# PID_MPS.net
KiCad netlist of a schematic drawn in EAGLE
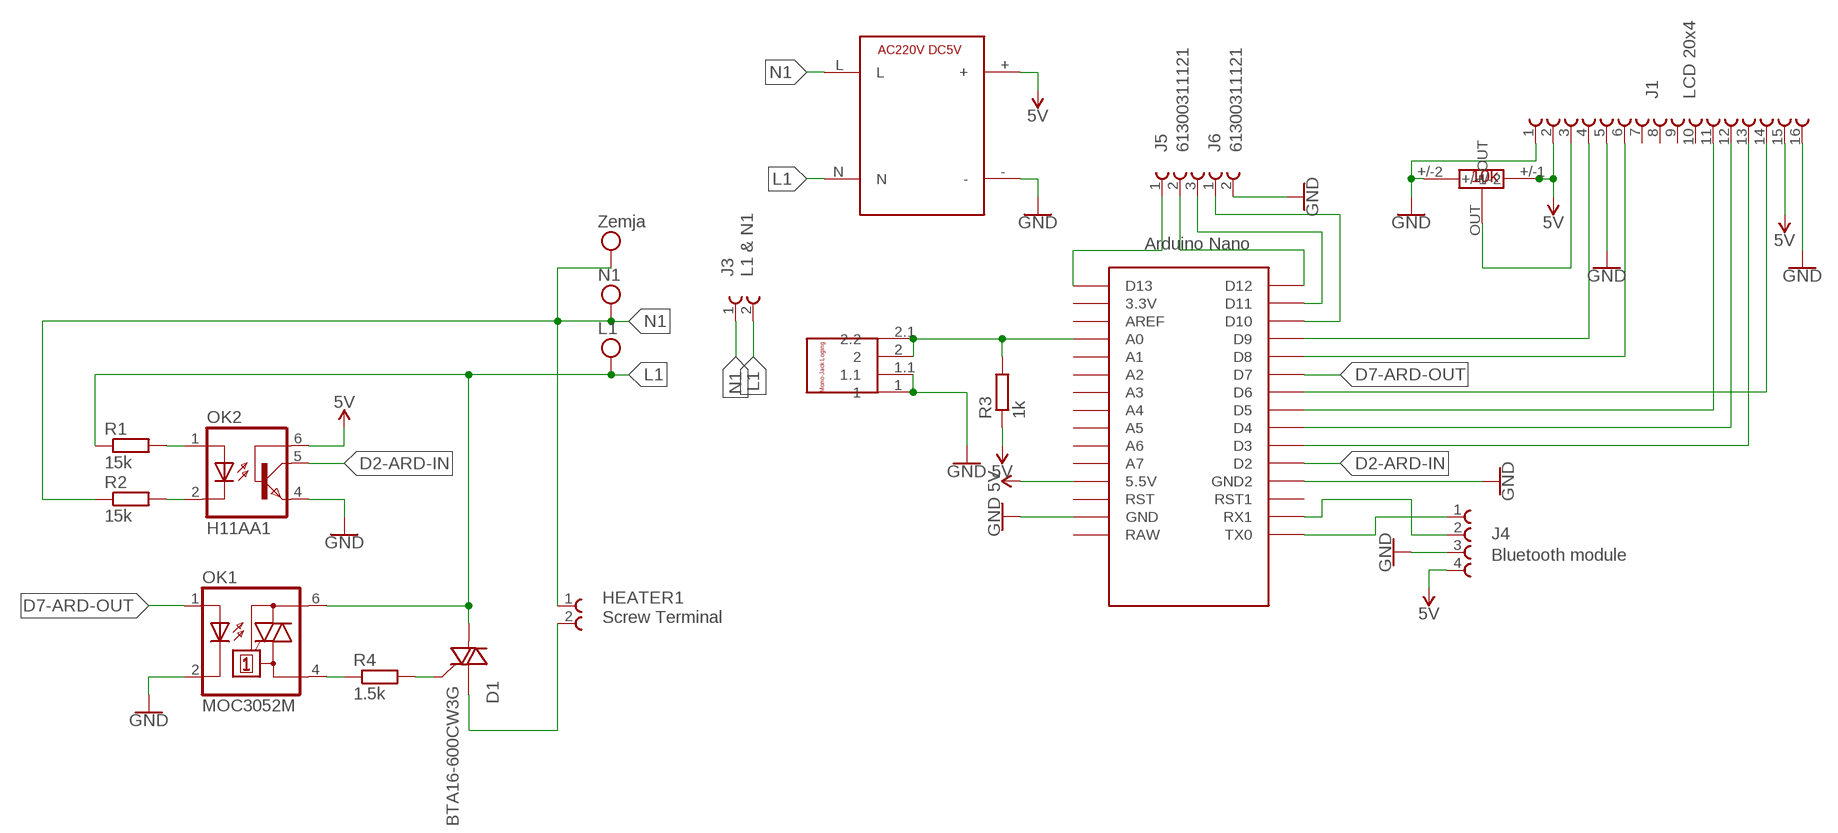
[diagram p0: schematic, sheet 1]

(export (version "E")
  (design (tool "Eeschema 10.0.6"))
  (components
    (comp (ref "D1")
      (value "BTA16-600CW3G")
      (footprint "eagle-import:TO254P1028X482X1968-3")
      (fields (field (name "MF") "Littelfuse Inc."))
      (libsource (lib "eagle-import") (part "BTA16-600CW3G"))
    )
    (comp (ref "HEATER1")
      (value "Screw Terminal")
      (footprint "eagle-import:691102710002")
      (fields (field (name "MF") "Wurth Electronics") (field (name "MP") "691102710002"))
      (libsource (lib "eagle-import") (part "691102710002"))
    )
    (comp (ref "J1")
      (value "LCD 20x4")
      (footprint "eagle-import:61301611121")
      (fields (field (name "MF") "Wurth Electronics") (field (name "MP") "61301611121"))
      (libsource (lib "eagle-import") (part "61301611121"))
    )
    (comp (ref "J3")
      (value "L1 & N1")
      (footprint "eagle-import:691102710002")
      (fields (field (name "MF") "Wurth Electronics") (field (name "MP") "691102710002"))
      (libsource (lib "eagle-import") (part "691102710002"))
    )
    (comp (ref "J4")
      (value "Bluetooth module")
      (footprint "eagle-import:61300411121")
      (fields (field (name "MF") "Wurth") (field (name "MP") "61300411121"))
      (libsource (lib "eagle-import") (part "61300411121"))
    )
    (comp (ref "J5")
      (value "61300311121")
      (footprint "eagle-import:61300311121")
      (fields (field (name "MF") "Wurth Electronics"))
      (libsource (lib "eagle-import") (part "61300311121 Letvici (cesel 3pin)_61300311121"))
    )
    (comp (ref "J6")
      (value "61300311121")
      (footprint "eagle-import:61300311121")
      (fields (field (name "MF") "Wurth Electronics"))
      (libsource (lib "eagle-import") (part "61300311121"))
    )
    (comp (ref "OK1")
      (value "MOC3052M")
      (footprint "eagle-import:DIL06")
      (fields (field (name "MF") "FAIRCHILD SEMICONDUCTOR") (field (name "MPN") "MOC3042-M"))
      (libsource (lib "eagle-import") (part "MOC3042M"))
    )
    (comp (ref "OK2")
      (value "H11AA1")
      (footprint "eagle-import:DIL06")
      (fields (field (name "MPN") "H11A1-M"))
      (libsource (lib "eagle-import") (part "H11A?M1"))
    )
    (comp (ref "R1")
      (value "15k")
      (footprint "eagle-import:0207_10")
      (libsource (lib "eagle-import") (part "R0207/10"))
    )
    (comp (ref "R2")
      (value "15k")
      (footprint "eagle-import:0207_10")
      (libsource (lib "eagle-import") (part "R0207/10"))
    )
    (comp (ref "R3")
      (value "1k")
      (footprint "eagle-import:0207_10")
      (libsource (lib "eagle-import") (part "R0207/10"))
    )
    (comp (ref "R4")
      (value "1.5k")
      (footprint "eagle-import:0207_10")
      (libsource (lib "eagle-import") (part "R0207/10"))
    )
    (comp (ref "U$1")
      (value "NANO")
      (footprint "eagle-import:NANO")
      (libsource (lib "eagle-import") (part "NANO"))
    )
    (comp (ref "U$2")
      (value "AC220V-DC5V220V-5VALIEXPESS")
      (footprint "eagle-import:220AC-5DC")
      (libsource (lib "eagle-import") (part "AC220V-DC5V220V-5VALIEXPESS"))
    )
    (comp (ref "U$3")
      (value "POTENCIOMETAR-GACPOTENCIOMETAR-GAC")
      (footprint "eagle-import:POTENCIOMETAR-GAC")
      (libsource (lib "eagle-import") (part "POTENCIOMETAR-GACPOTENCIOMETAR-GAC"))
    )
    (comp (ref "U$4")
      (value "MONO-JACK-LOGING")
      (footprint "eagle-import:MONO-JACK-LOGING")
      (libsource (lib "eagle-import") (part "MONO-JACK-LOGING"))
    )
  )
  (nets
    (net (code "1") (name "5V") (class "Default")
      (node (ref "J1") (pin "15") (pinfunction "15_15") (pintype "passive"))
      (node (ref "J1") (pin "2") (pinfunction "2_2") (pintype "passive"))
      (node (ref "J4") (pin "4") (pinfunction "4_4") (pintype "passive"))
      (node (ref "OK2") (pin "6") (pinfunction "BAS_6") (pintype "passive"))
      (node (ref "R3") (pin "1") (pinfunction "1_1") (pintype "passive"))
      (node (ref "U$1") (pin "5V") (pinfunction "5.5V_5V") (pintype "bidirectional"))
      (node (ref "U$2") (pin "+") (pinfunction "+_+") (pintype "bidirectional"))
      (node (ref "U$3") (pin "+/-1") (pinfunction "+/-1_+/-1") (pintype "bidirectional"))
    )
    (net (code "2") (name "D2-ARD-IN") (class "Default")
      (node (ref "OK2") (pin "5") (pinfunction "COL_5") (pintype "passive"))
      (node (ref "U$1") (pin "D2") (pinfunction "D2_D2") (pintype "bidirectional"))
    )
    (net (code "3") (name "D7-ARD-OUT") (class "Default")
      (node (ref "OK1") (pin "1") (pinfunction "A_1") (pintype "passive"))
      (node (ref "U$1") (pin "D7") (pinfunction "D7_D7") (pintype "bidirectional"))
    )
    (net (code "4") (name "GND") (class "Default")
      (node (ref "J1") (pin "1") (pinfunction "1_1") (pintype "passive"))
      (node (ref "J1") (pin "16") (pinfunction "16_16") (pintype "passive"))
      (node (ref "J1") (pin "5") (pinfunction "5_5") (pintype "passive"))
      (node (ref "J4") (pin "3") (pinfunction "3_3") (pintype "passive"))
      (node (ref "J6") (pin "2") (pinfunction "2_2") (pintype "passive"))
      (node (ref "OK1") (pin "2") (pinfunction "C_2") (pintype "passive"))
      (node (ref "OK2") (pin "4") (pinfunction "EMI_4") (pintype "passive"))
      (node (ref "U$1") (pin "GND") (pinfunction "GND_GND") (pintype "bidirectional"))
      (node (ref "U$1") (pin "GND1") (pinfunction "GND2_GND1") (pintype "bidirectional"))
      (node (ref "U$2") (pin "-") (pinfunction "-_-") (pintype "bidirectional"))
      (node (ref "U$3") (pin "+/-2") (pinfunction "+/-2_+/-2") (pintype "bidirectional"))
      (node (ref "U$4") (pin "1") (pinfunction "1_1") (pintype "bidirectional"))
      (node (ref "U$4") (pin "1.1") (pinfunction "1.1_1.1") (pintype "bidirectional"))
    )
    (net (code "5") (name "L1") (class "Default")
      (node (ref "D1") (pin "2") (pinfunction "MT2_2") (pintype "passive"))
      (node (ref "J3") (pin "2") (pinfunction "2_2") (pintype "passive"))
      (node (ref "OK1") (pin "6") (pinfunction "A2_6") (pintype "passive"))
      (node (ref "R1") (pin "1") (pinfunction "1_1") (pintype "passive"))
      (node (ref "U$2") (pin "N") (pinfunction "N_N") (pintype "bidirectional"))
    )
    (net (code "6") (name "N1") (class "Default")
      (node (ref "HEATER1") (pin "1") (pinfunction "1_1") (pintype "passive"))
      (node (ref "J3") (pin "1") (pinfunction "1_1") (pintype "passive"))
      (node (ref "R2") (pin "1") (pinfunction "1_1") (pintype "passive"))
      (node (ref "U$2") (pin "L") (pinfunction "L_L") (pintype "bidirectional"))
    )
    (net (code "7") (name "Net-(D1-G)") (class "Default")
      (node (ref "D1") (pin "3") (pinfunction "G_3") (pintype "passive"))
      (node (ref "R4") (pin "2") (pinfunction "2_2") (pintype "passive"))
    )
    (net (code "8") (name "Net-(D1-MT1)") (class "Default")
      (node (ref "D1") (pin "1") (pinfunction "MT1_1") (pintype "passive"))
      (node (ref "HEATER1") (pin "2") (pinfunction "2_2") (pintype "passive"))
    )
    (net (code "9") (name "Net-(J1-Pad3)") (class "Default")
      (node (ref "J1") (pin "3") (pinfunction "3_3") (pintype "passive"))
      (node (ref "U$3") (pin "OUT") (pinfunction "OUT_OUT") (pintype "bidirectional"))
    )
    (net (code "10") (name "Net-(J1-Pad4)") (class "Default")
      (node (ref "J1") (pin "4") (pinfunction "4_4") (pintype "passive"))
      (node (ref "U$1") (pin "D9") (pinfunction "D9_D9") (pintype "bidirectional"))
    )
    (net (code "11") (name "Net-(J1-Pad6)") (class "Default")
      (node (ref "J1") (pin "6") (pinfunction "6_6") (pintype "passive"))
      (node (ref "U$1") (pin "D8") (pinfunction "D8_D8") (pintype "bidirectional"))
    )
    (net (code "12") (name "Net-(J1-Pad11)") (class "Default")
      (node (ref "J1") (pin "11") (pinfunction "11_11") (pintype "passive"))
      (node (ref "U$1") (pin "D5") (pinfunction "D5_D5") (pintype "bidirectional"))
    )
    (net (code "13") (name "Net-(J1-Pad12)") (class "Default")
      (node (ref "J1") (pin "12") (pinfunction "12_12") (pintype "passive"))
      (node (ref "U$1") (pin "D4") (pinfunction "D4_D4") (pintype "bidirectional"))
    )
    (net (code "14") (name "Net-(J1-Pad13)") (class "Default")
      (node (ref "J1") (pin "13") (pinfunction "13_13") (pintype "passive"))
      (node (ref "U$1") (pin "D3") (pinfunction "D3_D3") (pintype "bidirectional"))
    )
    (net (code "15") (name "Net-(J1-Pad14)") (class "Default")
      (node (ref "J1") (pin "14") (pinfunction "14_14") (pintype "passive"))
      (node (ref "U$1") (pin "D6") (pinfunction "D6_D6") (pintype "bidirectional"))
    )
    (net (code "16") (name "Net-(J4-Pad1)") (class "Default")
      (node (ref "J4") (pin "1") (pinfunction "1_1") (pintype "passive"))
      (node (ref "U$1") (pin "TX0") (pinfunction "TX0_TX0") (pintype "bidirectional"))
    )
    (net (code "17") (name "Net-(J4-Pad2)") (class "Default")
      (node (ref "J4") (pin "2") (pinfunction "2_2") (pintype "passive"))
      (node (ref "U$1") (pin "RX1") (pinfunction "RX1_RX1") (pintype "bidirectional"))
    )
    (net (code "18") (name "Net-(J5-Pad1)") (class "Default")
      (node (ref "J5") (pin "1") (pinfunction "1_1") (pintype "passive"))
      (node (ref "U$1") (pin "D13") (pinfunction "D13_D13") (pintype "bidirectional"))
    )
    (net (code "19") (name "Net-(J5-Pad2)") (class "Default")
      (node (ref "J5") (pin "2") (pinfunction "2_2") (pintype "passive"))
      (node (ref "U$1") (pin "D12") (pinfunction "D12_D12") (pintype "bidirectional"))
    )
    (net (code "20") (name "Net-(J5-Pad3)") (class "Default")
      (node (ref "J5") (pin "3") (pinfunction "3_3") (pintype "passive"))
      (node (ref "U$1") (pin "D11") (pinfunction "D11_D11") (pintype "bidirectional"))
    )
    (net (code "21") (name "Net-(J6-Pad1)") (class "Default")
      (node (ref "J6") (pin "1") (pinfunction "1_1") (pintype "passive"))
      (node (ref "U$1") (pin "D10") (pinfunction "D10_D10") (pintype "bidirectional"))
    )
    (net (code "22") (name "Net-(OK1-A1)") (class "Default")
      (node (ref "OK1") (pin "4") (pinfunction "A1_4") (pintype "passive"))
      (node (ref "R4") (pin "1") (pinfunction "1_1") (pintype "passive"))
    )
    (net (code "23") (name "Net-(OK2-A)") (class "Default")
      (node (ref "OK2") (pin "1") (pinfunction "A_1") (pintype "passive"))
      (node (ref "R1") (pin "2") (pinfunction "2_2") (pintype "passive"))
    )
    (net (code "24") (name "Net-(OK2-C)") (class "Default")
      (node (ref "OK2") (pin "2") (pinfunction "C_2") (pintype "passive"))
      (node (ref "R2") (pin "2") (pinfunction "2_2") (pintype "passive"))
    )
    (net (code "25") (name "Net-(U$4-2.2)") (class "Default")
      (node (ref "R3") (pin "2") (pinfunction "2_2") (pintype "passive"))
      (node (ref "U$1") (pin "A0") (pinfunction "A0_A0") (pintype "bidirectional"))
      (node (ref "U$4") (pin "2") (pinfunction "2_2") (pintype "bidirectional"))
      (node (ref "U$4") (pin "2.1") (pinfunction "2.2_2.1") (pintype "bidirectional"))
    )
    (net (code "26") (name "unconnected-(J1-Pad7)") (class "Default")
      (node (ref "J1") (pin "7") (pinfunction "7_7") (pintype "passive"))
    )
    (net (code "27") (name "unconnected-(J1-Pad8)") (class "Default")
      (node (ref "J1") (pin "8") (pinfunction "8_8") (pintype "passive"))
    )
    (net (code "28") (name "unconnected-(J1-Pad9)") (class "Default")
      (node (ref "J1") (pin "9") (pinfunction "9_9") (pintype "passive"))
    )
    (net (code "29") (name "unconnected-(J1-Pad10)") (class "Default")
      (node (ref "J1") (pin "10") (pinfunction "10_10") (pintype "passive"))
    )
    (net (code "30") (name "unconnected-(U$1-Pad3.3V)") (class "Default")
      (node (ref "U$1") (pin "3.3V") (pinfunction "3.3V_3.3V") (pintype "bidirectional"))
    )
    (net (code "31") (name "unconnected-(U$1-PadA1)") (class "Default")
      (node (ref "U$1") (pin "A1") (pinfunction "A1_A1") (pintype "bidirectional"))
    )
    (net (code "32") (name "unconnected-(U$1-PadA2)") (class "Default")
      (node (ref "U$1") (pin "A2") (pinfunction "A2_A2") (pintype "bidirectional"))
    )
    (net (code "33") (name "unconnected-(U$1-PadA3)") (class "Default")
      (node (ref "U$1") (pin "A3") (pinfunction "A3_A3") (pintype "bidirectional"))
    )
    (net (code "34") (name "unconnected-(U$1-PadA4)") (class "Default")
      (node (ref "U$1") (pin "A4") (pinfunction "A4_A4") (pintype "bidirectional"))
    )
    (net (code "35") (name "unconnected-(U$1-PadA5)") (class "Default")
      (node (ref "U$1") (pin "A5") (pinfunction "A5_A5") (pintype "bidirectional"))
    )
    (net (code "36") (name "unconnected-(U$1-PadA6)") (class "Default")
      (node (ref "U$1") (pin "A6") (pinfunction "A6_A6") (pintype "bidirectional"))
    )
    (net (code "37") (name "unconnected-(U$1-PadA7)") (class "Default")
      (node (ref "U$1") (pin "A7") (pinfunction "A7_A7") (pintype "bidirectional"))
    )
    (net (code "38") (name "unconnected-(U$1-PadAREF)") (class "Default")
      (node (ref "U$1") (pin "AREF") (pinfunction "AREF_AREF") (pintype "bidirectional"))
    )
    (net (code "39") (name "unconnected-(U$1-PadICSP1)") (class "Default")
      (node (ref "U$1") (pin "ICSP1") (pinfunction "ICSP1_ICSP1") (pintype "bidirectional"))
    )
    (net (code "40") (name "unconnected-(U$1-PadICSP2)") (class "Default")
      (node (ref "U$1") (pin "ICSP2") (pinfunction "ICSP2_ICSP2") (pintype "bidirectional"))
    )
    (net (code "41") (name "unconnected-(U$1-PadICSP3)") (class "Default")
      (node (ref "U$1") (pin "ICSP3") (pinfunction "ICSP3_ICSP3") (pintype "bidirectional"))
    )
    (net (code "42") (name "unconnected-(U$1-PadICSP4)") (class "Default")
      (node (ref "U$1") (pin "ICSP4") (pinfunction "ICSP4_ICSP4") (pintype "bidirectional"))
    )
    (net (code "43") (name "unconnected-(U$1-PadICSP5)") (class "Default")
      (node (ref "U$1") (pin "ICSP5") (pinfunction "ICSP5_ICSP5") (pintype "bidirectional"))
    )
    (net (code "44") (name "unconnected-(U$1-PadICSP6)") (class "Default")
      (node (ref "U$1") (pin "ICSP6") (pinfunction "ICSP6_ICSP6") (pintype "bidirectional"))
    )
    (net (code "45") (name "unconnected-(U$1-PadRAW)") (class "Default")
      (node (ref "U$1") (pin "RAW") (pinfunction "RAW_RAW") (pintype "bidirectional"))
    )
    (net (code "46") (name "unconnected-(U$1-PadRST)") (class "Default")
      (node (ref "U$1") (pin "RST") (pinfunction "RST_RST") (pintype "bidirectional"))
    )
    (net (code "47") (name "unconnected-(U$1-PadRST1)") (class "Default")
      (node (ref "U$1") (pin "RST1") (pinfunction "RST1_RST1") (pintype "bidirectional"))
    )
  )
)
